# init_test.net
KiCad netlist of a schematic drawn in EAGLE
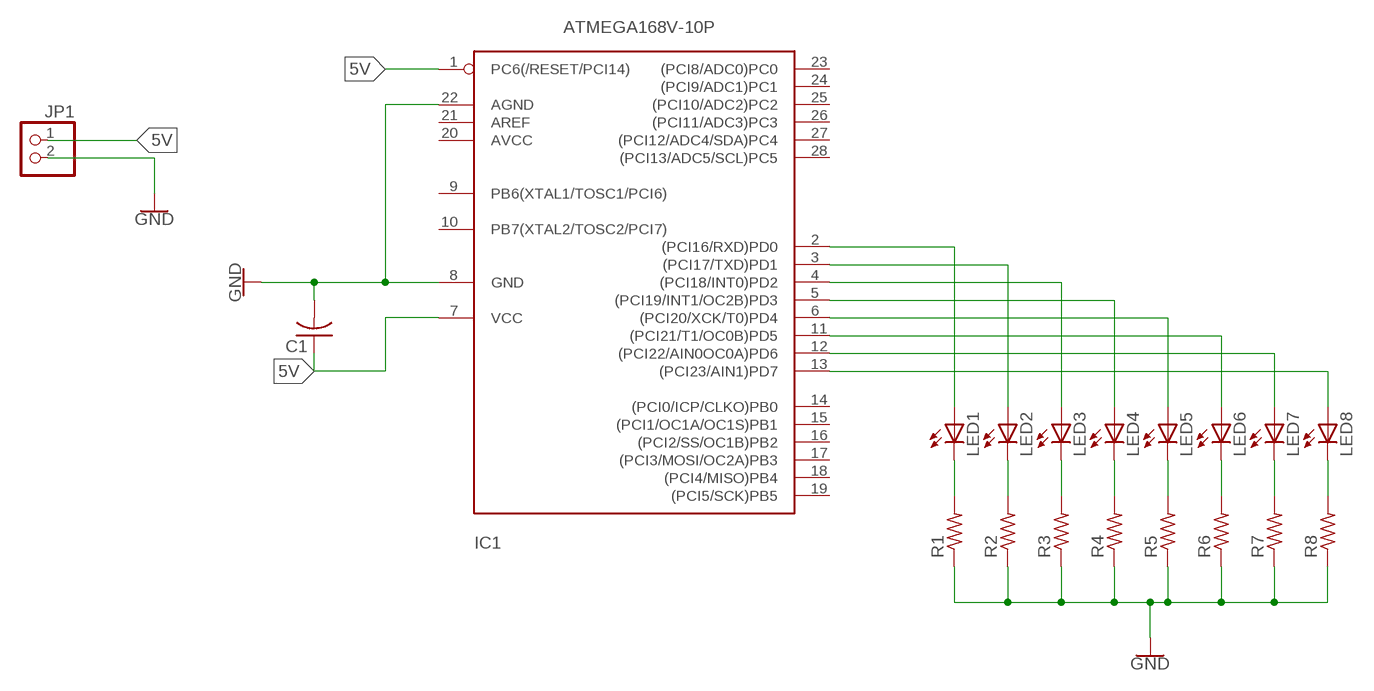
[diagram p0: schematic, sheet 1]

(export (version "E")
  (design (tool "Eeschema 10.0.6"))
  (components
    (comp (ref "C1")
      (value "C-US025-030X050")
      (footprint "eagle-import:C025-030X050")
      (libsource (lib "eagle-import") (part "C-US025-030X050"))
    )
    (comp (ref "IC1")
      (value "ATMEGA168V-10P")
      (footprint "eagle-import:DIL28-3")
      (libsource (lib "eagle-import") (part "ATMEGA168PV-10"))
    )
    (comp (ref "JP1")
      (value "PINHD-1X2")
      (footprint "eagle-import:1X02")
      (libsource (lib "eagle-import") (part "PINHD-1X2"))
    )
    (comp (ref "LED1")
      (value "LED3MM")
      (footprint "eagle-import:LED3MM")
      (libsource (lib "eagle-import") (part "LED3MM"))
    )
    (comp (ref "LED2")
      (value "LED3MM")
      (footprint "eagle-import:LED3MM")
      (libsource (lib "eagle-import") (part "LED3MM"))
    )
    (comp (ref "LED3")
      (value "LED3MM")
      (footprint "eagle-import:LED3MM")
      (libsource (lib "eagle-import") (part "LED3MM"))
    )
    (comp (ref "LED4")
      (value "LED3MM")
      (footprint "eagle-import:LED3MM")
      (libsource (lib "eagle-import") (part "LED3MM"))
    )
    (comp (ref "LED5")
      (value "LED3MM")
      (footprint "eagle-import:LED3MM")
      (libsource (lib "eagle-import") (part "LED3MM"))
    )
    (comp (ref "LED6")
      (value "LED3MM")
      (footprint "eagle-import:LED3MM")
      (libsource (lib "eagle-import") (part "LED3MM"))
    )
    (comp (ref "LED7")
      (value "LED3MM")
      (footprint "eagle-import:LED3MM")
      (libsource (lib "eagle-import") (part "LED3MM"))
    )
    (comp (ref "LED8")
      (value "LED3MM")
      (footprint "eagle-import:LED3MM")
      (libsource (lib "eagle-import") (part "LED3MM"))
    )
    (comp (ref "R1")
      (value "R-US_0207/7")
      (footprint "eagle-import:0207_7")
      (libsource (lib "eagle-import") (part "R-US_0207/7"))
    )
    (comp (ref "R2")
      (value "R-US_0207/7")
      (footprint "eagle-import:0207_7")
      (libsource (lib "eagle-import") (part "R-US_0207/7"))
    )
    (comp (ref "R3")
      (value "R-US_0207/7")
      (footprint "eagle-import:0207_7")
      (libsource (lib "eagle-import") (part "R-US_0207/7"))
    )
    (comp (ref "R4")
      (value "R-US_0207/7")
      (footprint "eagle-import:0207_7")
      (libsource (lib "eagle-import") (part "R-US_0207/7"))
    )
    (comp (ref "R5")
      (value "R-US_0207/7")
      (footprint "eagle-import:0207_7")
      (libsource (lib "eagle-import") (part "R-US_0207/7"))
    )
    (comp (ref "R6")
      (value "R-US_0207/7")
      (footprint "eagle-import:0207_7")
      (libsource (lib "eagle-import") (part "R-US_0207/7"))
    )
    (comp (ref "R7")
      (value "R-US_0207/7")
      (footprint "eagle-import:0207_7")
      (libsource (lib "eagle-import") (part "R-US_0207/7"))
    )
    (comp (ref "R8")
      (value "R-US_0207/7")
      (footprint "eagle-import:0207_7")
      (libsource (lib "eagle-import") (part "R-US_0207/7"))
    )
  )
  (nets
    (net (code "1") (name "5V") (class "Default")
      (node (ref "C1") (pin "1") (pinfunction "1_1") (pintype "passive"))
      (node (ref "IC1") (pin "1") (pinfunction "PC6(/RESET/PCI14)_1") (pintype "bidirectional"))
      (node (ref "IC1") (pin "7") (pinfunction "VCC_7") (pintype "bidirectional"))
      (node (ref "JP1") (pin "1") (pinfunction "1_1") (pintype "passive"))
    )
    (net (code "2") (name "GND") (class "Default")
      (node (ref "C1") (pin "2") (pinfunction "2_2") (pintype "passive"))
      (node (ref "IC1") (pin "22") (pinfunction "AGND_22") (pintype "bidirectional"))
      (node (ref "IC1") (pin "8") (pinfunction "GND_8") (pintype "bidirectional"))
      (node (ref "JP1") (pin "2") (pinfunction "2_2") (pintype "passive"))
      (node (ref "R1") (pin "1") (pinfunction "1_1") (pintype "passive"))
      (node (ref "R2") (pin "1") (pinfunction "1_1") (pintype "passive"))
      (node (ref "R3") (pin "1") (pinfunction "1_1") (pintype "passive"))
      (node (ref "R4") (pin "1") (pinfunction "1_1") (pintype "passive"))
      (node (ref "R5") (pin "1") (pinfunction "1_1") (pintype "passive"))
      (node (ref "R6") (pin "1") (pinfunction "1_1") (pintype "passive"))
      (node (ref "R7") (pin "1") (pinfunction "1_1") (pintype "passive"))
      (node (ref "R8") (pin "1") (pinfunction "1_1") (pintype "passive"))
    )
    (net (code "3") (name "Net-(IC1-(PCI16{slash}RXD)PD0)") (class "Default")
      (node (ref "IC1") (pin "2") (pinfunction "(PCI16/RXD)PD0_2") (pintype "bidirectional"))
      (node (ref "LED1") (pin "A") (pinfunction "A_A") (pintype "passive"))
    )
    (net (code "4") (name "Net-(IC1-(PCI17{slash}TXD)PD1)") (class "Default")
      (node (ref "IC1") (pin "3") (pinfunction "(PCI17/TXD)PD1_3") (pintype "bidirectional"))
      (node (ref "LED2") (pin "A") (pinfunction "A_A") (pintype "passive"))
    )
    (net (code "5") (name "Net-(IC1-(PCI18{slash}INT0)PD2)") (class "Default")
      (node (ref "IC1") (pin "4") (pinfunction "(PCI18/INT0)PD2_4") (pintype "bidirectional"))
      (node (ref "LED3") (pin "A") (pinfunction "A_A") (pintype "passive"))
    )
    (net (code "6") (name "Net-(IC1-(PCI19{slash}INT1{slash}OC2B)PD3)") (class "Default")
      (node (ref "IC1") (pin "5") (pinfunction "(PCI19/INT1/OC2B)PD3_5") (pintype "bidirectional"))
      (node (ref "LED4") (pin "A") (pinfunction "A_A") (pintype "passive"))
    )
    (net (code "7") (name "Net-(IC1-(PCI20{slash}XCK{slash}T0)PD4)") (class "Default")
      (node (ref "IC1") (pin "6") (pinfunction "(PCI20/XCK/T0)PD4_6") (pintype "bidirectional"))
      (node (ref "LED5") (pin "A") (pinfunction "A_A") (pintype "passive"))
    )
    (net (code "8") (name "Net-(IC1-(PCI21{slash}T1{slash}OC0B)PD5)") (class "Default")
      (node (ref "IC1") (pin "11") (pinfunction "(PCI21/T1/OC0B)PD5_11") (pintype "bidirectional"))
      (node (ref "LED6") (pin "A") (pinfunction "A_A") (pintype "passive"))
    )
    (net (code "9") (name "Net-(IC1-(PCI22{slash}AIN0OC0A)PD6)") (class "Default")
      (node (ref "IC1") (pin "12") (pinfunction "(PCI22/AIN0OC0A)PD6_12") (pintype "bidirectional"))
      (node (ref "LED7") (pin "A") (pinfunction "A_A") (pintype "passive"))
    )
    (net (code "10") (name "Net-(IC1-(PCI23{slash}AIN1)PD7)") (class "Default")
      (node (ref "IC1") (pin "13") (pinfunction "(PCI23/AIN1)PD7_13") (pintype "bidirectional"))
      (node (ref "LED8") (pin "A") (pinfunction "A_A") (pintype "passive"))
    )
    (net (code "11") (name "Net-(LED1-C)") (class "Default")
      (node (ref "LED1") (pin "K") (pinfunction "C_K") (pintype "passive"))
      (node (ref "R1") (pin "2") (pinfunction "2_2") (pintype "passive"))
    )
    (net (code "12") (name "Net-(LED2-C)") (class "Default")
      (node (ref "LED2") (pin "K") (pinfunction "C_K") (pintype "passive"))
      (node (ref "R2") (pin "2") (pinfunction "2_2") (pintype "passive"))
    )
    (net (code "13") (name "Net-(LED3-C)") (class "Default")
      (node (ref "LED3") (pin "K") (pinfunction "C_K") (pintype "passive"))
      (node (ref "R3") (pin "2") (pinfunction "2_2") (pintype "passive"))
    )
    (net (code "14") (name "Net-(LED4-C)") (class "Default")
      (node (ref "LED4") (pin "K") (pinfunction "C_K") (pintype "passive"))
      (node (ref "R4") (pin "2") (pinfunction "2_2") (pintype "passive"))
    )
    (net (code "15") (name "Net-(LED5-C)") (class "Default")
      (node (ref "LED5") (pin "K") (pinfunction "C_K") (pintype "passive"))
      (node (ref "R5") (pin "2") (pinfunction "2_2") (pintype "passive"))
    )
    (net (code "16") (name "Net-(LED6-C)") (class "Default")
      (node (ref "LED6") (pin "K") (pinfunction "C_K") (pintype "passive"))
      (node (ref "R6") (pin "2") (pinfunction "2_2") (pintype "passive"))
    )
    (net (code "17") (name "Net-(LED7-C)") (class "Default")
      (node (ref "LED7") (pin "K") (pinfunction "C_K") (pintype "passive"))
      (node (ref "R7") (pin "2") (pinfunction "2_2") (pintype "passive"))
    )
    (net (code "18") (name "Net-(LED8-C)") (class "Default")
      (node (ref "LED8") (pin "K") (pinfunction "C_K") (pintype "passive"))
      (node (ref "R8") (pin "2") (pinfunction "2_2") (pintype "passive"))
    )
    (net (code "19") (name "unconnected-(IC1-(PCI0{slash}ICP{slash}CLKO)PB0-Pad14)") (class "Default")
      (node (ref "IC1") (pin "14") (pinfunction "(PCI0/ICP/CLKO)PB0_14") (pintype "bidirectional"))
    )
    (net (code "20") (name "unconnected-(IC1-(PCI1{slash}OC1A{slash}OC1S)PB1-Pad15)") (class "Default")
      (node (ref "IC1") (pin "15") (pinfunction "(PCI1/OC1A/OC1S)PB1_15") (pintype "bidirectional"))
    )
    (net (code "21") (name "unconnected-(IC1-(PCI2{slash}SS{slash}OC1B)PB2-Pad16)") (class "Default")
      (node (ref "IC1") (pin "16") (pinfunction "(PCI2/SS/OC1B)PB2_16") (pintype "bidirectional"))
    )
    (net (code "22") (name "unconnected-(IC1-(PCI3{slash}MOSI{slash}OC2A)PB3-Pad17)") (class "Default")
      (node (ref "IC1") (pin "17") (pinfunction "(PCI3/MOSI/OC2A)PB3_17") (pintype "bidirectional"))
    )
    (net (code "23") (name "unconnected-(IC1-(PCI4{slash}MISO)PB4-Pad18)") (class "Default")
      (node (ref "IC1") (pin "18") (pinfunction "(PCI4/MISO)PB4_18") (pintype "bidirectional"))
    )
    (net (code "24") (name "unconnected-(IC1-(PCI5{slash}SCK)PB5-Pad19)") (class "Default")
      (node (ref "IC1") (pin "19") (pinfunction "(PCI5/SCK)PB5_19") (pintype "bidirectional"))
    )
    (net (code "25") (name "unconnected-(IC1-(PCI8{slash}ADC0)PC0-Pad23)") (class "Default")
      (node (ref "IC1") (pin "23") (pinfunction "(PCI8/ADC0)PC0_23") (pintype "bidirectional"))
    )
    (net (code "26") (name "unconnected-(IC1-(PCI9{slash}ADC1)PC1-Pad24)") (class "Default")
      (node (ref "IC1") (pin "24") (pinfunction "(PCI9/ADC1)PC1_24") (pintype "bidirectional"))
    )
    (net (code "27") (name "unconnected-(IC1-(PCI10{slash}ADC2)PC2-Pad25)") (class "Default")
      (node (ref "IC1") (pin "25") (pinfunction "(PCI10/ADC2)PC2_25") (pintype "bidirectional"))
    )
    (net (code "28") (name "unconnected-(IC1-(PCI11{slash}ADC3)PC3-Pad26)") (class "Default")
      (node (ref "IC1") (pin "26") (pinfunction "(PCI11/ADC3)PC3_26") (pintype "bidirectional"))
    )
    (net (code "29") (name "unconnected-(IC1-(PCI12{slash}ADC4{slash}SDA)PC4-Pad27)") (class "Default")
      (node (ref "IC1") (pin "27") (pinfunction "(PCI12/ADC4/SDA)PC4_27") (pintype "bidirectional"))
    )
    (net (code "30") (name "unconnected-(IC1-(PCI13{slash}ADC5{slash}SCL)PC5-Pad28)") (class "Default")
      (node (ref "IC1") (pin "28") (pinfunction "(PCI13/ADC5/SCL)PC5_28") (pintype "bidirectional"))
    )
    (net (code "31") (name "unconnected-(IC1-AREF-Pad21)") (class "Default")
      (node (ref "IC1") (pin "21") (pinfunction "AREF_21") (pintype "bidirectional"))
    )
    (net (code "32") (name "unconnected-(IC1-AVCC-Pad20)") (class "Default")
      (node (ref "IC1") (pin "20") (pinfunction "AVCC_20") (pintype "bidirectional"))
    )
    (net (code "33") (name "unconnected-(IC1-PB6(XTAL1{slash}TOSC1{slash}PCI6)-Pad9)") (class "Default")
      (node (ref "IC1") (pin "9") (pinfunction "PB6(XTAL1/TOSC1/PCI6)_9") (pintype "bidirectional"))
    )
    (net (code "34") (name "unconnected-(IC1-PB7(XTAL2{slash}TOSC2{slash}PCI7)-Pad10)") (class "Default")
      (node (ref "IC1") (pin "10") (pinfunction "PB7(XTAL2/TOSC2/PCI7)_10") (pintype "bidirectional"))
    )
  )
)
